# Snippet_LM1117MP-3_3.net
KiCad netlist of a schematic drawn in Altium Designer
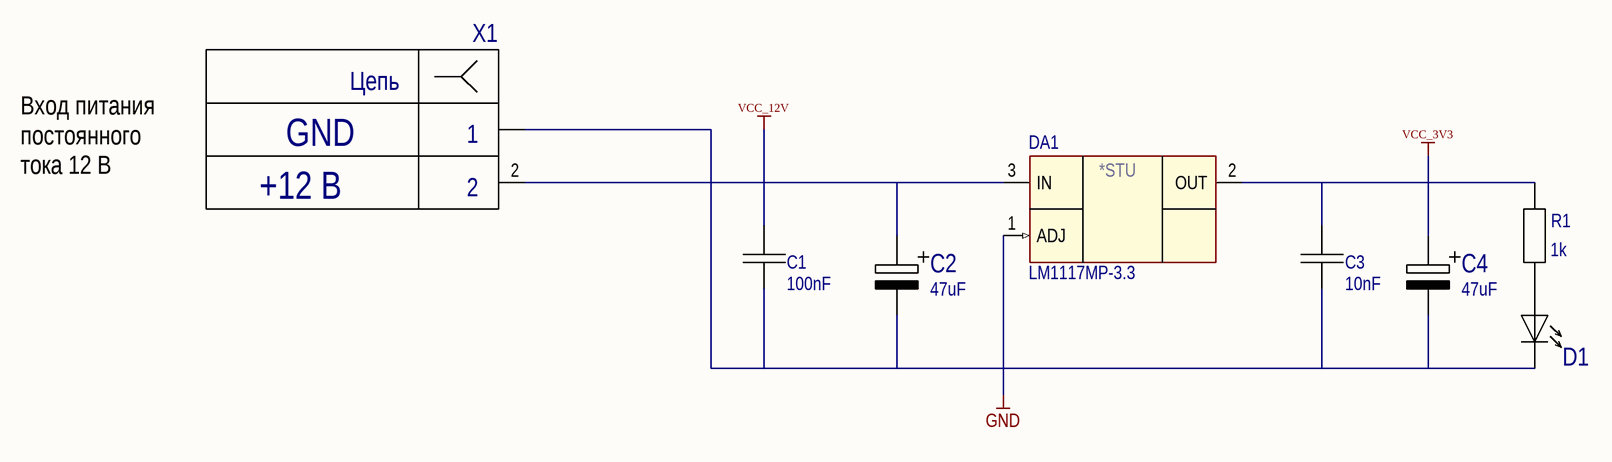
[diagram p0: Snippet_LM1117MP-3.3.SchDoc]

(export (version "E")
  (design (tool "Eeschema 10.0.6"))
  (components
    (comp (ref "C1")
      (value "100nF")
      (footprint "Capacitor_0805")
      (libsource (lib "Библиотека элементов") (part "Capacitor_0805"))
    )
    (comp (ref "C2")
      (value "47uF")
      (footprint "Capacitor_Electrolit_6.3x11")
      (libsource (lib "Библиотека элементов") (part "Capacitor+_6.3x11"))
    )
    (comp (ref "C3")
      (value "10nF")
      (footprint "Capacitor_0805")
      (libsource (lib "Библиотека элементов") (part "Capacitor_0805"))
    )
    (comp (ref "C4")
      (value "47uF")
      (footprint "CAPACITOR+_22uFx25V")
      (libsource (lib "Библиотека элементов") (part "Capacitor+_22uFx25V"))
    )
    (comp (ref "D1")
      (value "LED_2.54mm_R")
      (footprint "LED_2.54mm_R")
      (libsource (lib "Библиотека элементов") (part "LED_2.54mm_R"))
    )
    (comp (ref "DA1")
      (value "LM1117MP-3.3")
      (footprint "NCP1117_SOT223")
      (libsource (lib "Библиотека элементов") (part "LM1117MP-3.3"))
    )
    (comp (ref "R1")
      (value "1k")
      (footprint "RESISTOR_SMD0805")
      (libsource (lib "Библиотека элементов") (part "Resistor_0805"))
    )
    (comp (ref "X1")
      (value "Connector_DG350-3.5-02P-14")
      (footprint "CONNECTOR_DG350-3.5-02P-14")
      (libsource (lib "Библиотека элементов") (part "Connector_DG350-3.5-02P-14"))
    )
  )
  (nets
    (net (code "1") (name "GND") (class "Default")
      (node (ref "C1") (pin "2") (pinfunction "2_2") (pintype "passive"))
      (node (ref "C2") (pin "2") (pinfunction "2_2") (pintype "passive"))
      (node (ref "C3") (pin "2") (pinfunction "2_2") (pintype "passive"))
      (node (ref "C4") (pin "2") (pinfunction "2_2") (pintype "passive"))
      (node (ref "D1") (pin "1") (pinfunction "1_1") (pintype "passive"))
      (node (ref "DA1") (pin "1") (pinfunction "ADJ_1") (pintype "input"))
      (node (ref "X1") (pin "1") (pinfunction "1_1") (pintype "passive"))
    )
    (net (code "2") (name "Net-(D1-Pad2)") (class "Default")
      (node (ref "D1") (pin "2") (pinfunction "2_2") (pintype "passive"))
      (node (ref "R1") (pin "1") (pinfunction "1_1") (pintype "passive"))
    )
    (net (code "3") (name "VCC_3V3") (class "Default")
      (node (ref "C3") (pin "1") (pinfunction "1_1") (pintype "passive"))
      (node (ref "C4") (pin "1") (pinfunction "1_1") (pintype "passive"))
      (node (ref "DA1") (pin "2") (pinfunction "OUT_2") (pintype "power_in"))
      (node (ref "R1") (pin "2") (pinfunction "2_2") (pintype "passive"))
    )
    (net (code "4") (name "VCC_12V") (class "Default")
      (node (ref "C1") (pin "1") (pinfunction "1_1") (pintype "passive"))
      (node (ref "C2") (pin "1") (pinfunction "1_1") (pintype "passive"))
      (node (ref "DA1") (pin "3") (pinfunction "IN_3") (pintype "power_in"))
      (node (ref "X1") (pin "2") (pinfunction "2_2") (pintype "passive"))
    )
  )
)
